# analog_converter.net
KiCad netlist of a schematic drawn in Altium Designer
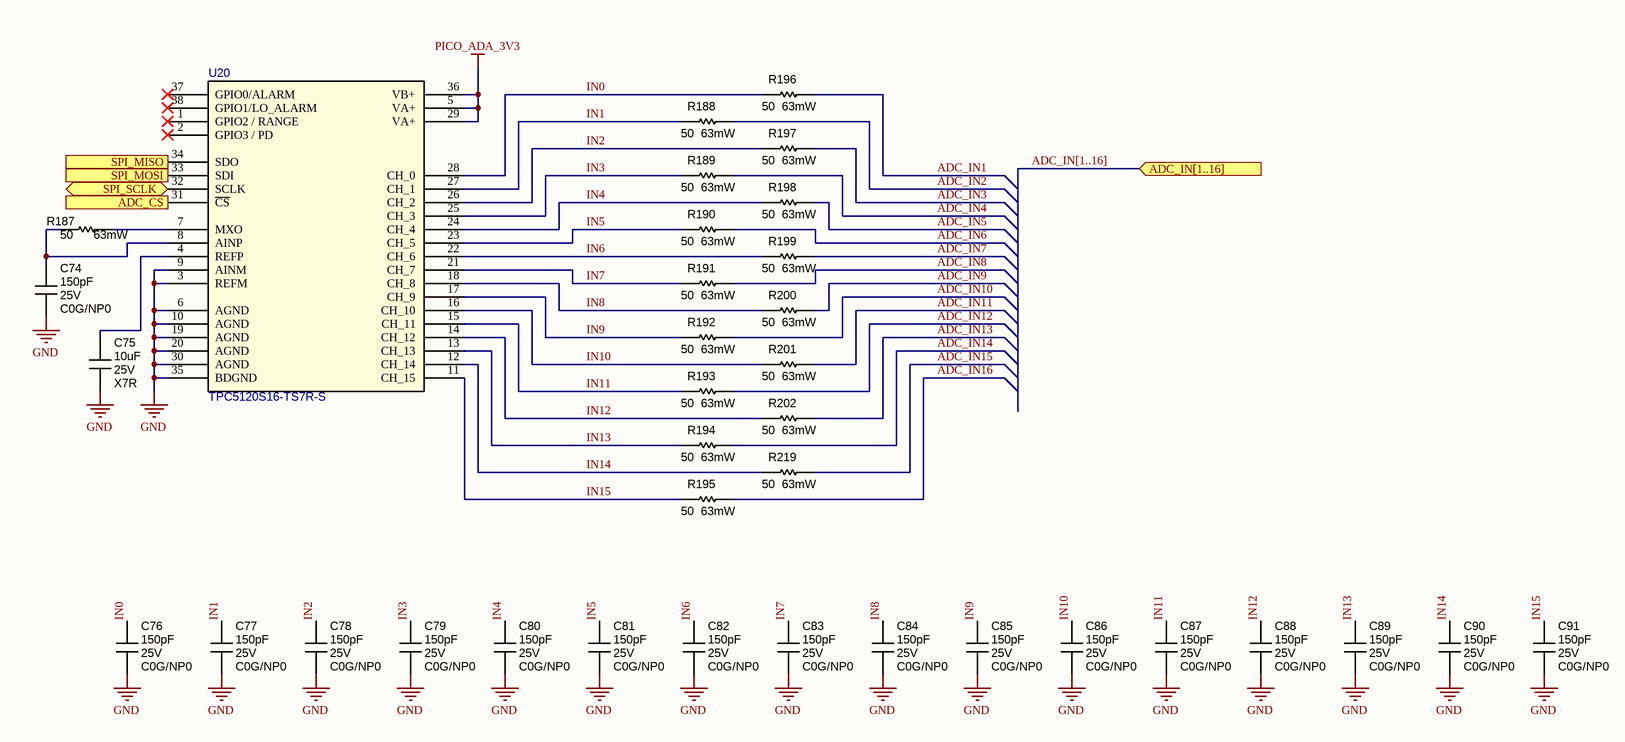
[diagram p0: analog_converter.SchDoc]

(export (version "E")
  (design (tool "Eeschema 10.0.6"))
  (components
    (comp (ref "C74")
      (value "150pF")
      (footprint "CAPC1005X06N")
      (description "CAP CER 150PF 25V C0G/NP0 0402")
      (fields
        (field (name "TOLERANCE") "5%")
        (field (name "MFR") "KEMET")
        (field (name "VOLTAGE RATING") "25V")
        (field (name "TEMP COEFF") "C0G/NP0")
      )
      (libsource (lib "General_Library") (part "CMP-004-0079"))
    )
    (comp (ref "C75")
      (value "10uF")
      (footprint "CAPC3225X28N")
      (description "CAP CER 10UF 25V X7R 1206")
      (fields
        (field (name "TOLERANCE") "10%")
        (field (name "MFR") "Murata Electronics")
        (field (name "VOLTAGE RATING") "25V")
        (field (name "TEMP COEFF") "X7R")
      )
      (libsource (lib "General_Library") (part "CMP-004-0004"))
    )
    (comp (ref "C76")
      (value "150pF")
      (footprint "CAPC1005X06N")
      (description "CAP CER 150PF 25V C0G/NP0 0402")
      (fields
        (field (name "TOLERANCE") "5%")
        (field (name "MFR") "KEMET")
        (field (name "VOLTAGE RATING") "25V")
        (field (name "TEMP COEFF") "C0G/NP0")
      )
      (libsource (lib "General_Library") (part "CMP-004-0079"))
    )
    (comp (ref "C77")
      (value "150pF")
      (footprint "CAPC1005X06N")
      (description "CAP CER 150PF 25V C0G/NP0 0402")
      (fields
        (field (name "TOLERANCE") "5%")
        (field (name "MFR") "KEMET")
        (field (name "VOLTAGE RATING") "25V")
        (field (name "TEMP COEFF") "C0G/NP0")
      )
      (libsource (lib "General_Library") (part "CMP-004-0079"))
    )
    (comp (ref "C78")
      (value "150pF")
      (footprint "CAPC1005X06N")
      (description "CAP CER 150PF 25V C0G/NP0 0402")
      (fields
        (field (name "TOLERANCE") "5%")
        (field (name "MFR") "KEMET")
        (field (name "VOLTAGE RATING") "25V")
        (field (name "TEMP COEFF") "C0G/NP0")
      )
      (libsource (lib "General_Library") (part "CMP-004-0079"))
    )
    (comp (ref "C79")
      (value "150pF")
      (footprint "CAPC1005X06N")
      (description "CAP CER 150PF 25V C0G/NP0 0402")
      (fields
        (field (name "TOLERANCE") "5%")
        (field (name "MFR") "KEMET")
        (field (name "VOLTAGE RATING") "25V")
        (field (name "TEMP COEFF") "C0G/NP0")
      )
      (libsource (lib "General_Library") (part "CMP-004-0079"))
    )
    (comp (ref "C80")
      (value "150pF")
      (footprint "CAPC1005X06N")
      (description "CAP CER 150PF 25V C0G/NP0 0402")
      (fields
        (field (name "TOLERANCE") "5%")
        (field (name "MFR") "KEMET")
        (field (name "VOLTAGE RATING") "25V")
        (field (name "TEMP COEFF") "C0G/NP0")
      )
      (libsource (lib "General_Library") (part "CMP-004-0079"))
    )
    (comp (ref "C81")
      (value "150pF")
      (footprint "CAPC1005X06N")
      (description "CAP CER 150PF 25V C0G/NP0 0402")
      (fields
        (field (name "TOLERANCE") "5%")
        (field (name "MFR") "KEMET")
        (field (name "VOLTAGE RATING") "25V")
        (field (name "TEMP COEFF") "C0G/NP0")
      )
      (libsource (lib "General_Library") (part "CMP-004-0079"))
    )
    (comp (ref "C82")
      (value "150pF")
      (footprint "CAPC1005X06N")
      (description "CAP CER 150PF 25V C0G/NP0 0402")
      (fields
        (field (name "TOLERANCE") "5%")
        (field (name "MFR") "KEMET")
        (field (name "VOLTAGE RATING") "25V")
        (field (name "TEMP COEFF") "C0G/NP0")
      )
      (libsource (lib "General_Library") (part "CMP-004-0079"))
    )
    (comp (ref "C83")
      (value "150pF")
      (footprint "CAPC1005X06N")
      (description "CAP CER 150PF 25V C0G/NP0 0402")
      (fields
        (field (name "TOLERANCE") "5%")
        (field (name "MFR") "KEMET")
        (field (name "VOLTAGE RATING") "25V")
        (field (name "TEMP COEFF") "C0G/NP0")
      )
      (libsource (lib "General_Library") (part "CMP-004-0079"))
    )
    (comp (ref "C84")
      (value "150pF")
      (footprint "CAPC1005X06N")
      (description "CAP CER 150PF 25V C0G/NP0 0402")
      (fields
        (field (name "TOLERANCE") "5%")
        (field (name "MFR") "KEMET")
        (field (name "VOLTAGE RATING") "25V")
        (field (name "TEMP COEFF") "C0G/NP0")
      )
      (libsource (lib "General_Library") (part "CMP-004-0079"))
    )
    (comp (ref "C85")
      (value "150pF")
      (footprint "CAPC1005X06N")
      (description "CAP CER 150PF 25V C0G/NP0 0402")
      (fields
        (field (name "TOLERANCE") "5%")
        (field (name "MFR") "KEMET")
        (field (name "VOLTAGE RATING") "25V")
        (field (name "TEMP COEFF") "C0G/NP0")
      )
      (libsource (lib "General_Library") (part "CMP-004-0079"))
    )
    (comp (ref "C86")
      (value "150pF")
      (footprint "CAPC1005X06N")
      (description "CAP CER 150PF 25V C0G/NP0 0402")
      (fields
        (field (name "TOLERANCE") "5%")
        (field (name "MFR") "KEMET")
        (field (name "VOLTAGE RATING") "25V")
        (field (name "TEMP COEFF") "C0G/NP0")
      )
      (libsource (lib "General_Library") (part "CMP-004-0079"))
    )
    (comp (ref "C87")
      (value "150pF")
      (footprint "CAPC1005X06N")
      (description "CAP CER 150PF 25V C0G/NP0 0402")
      (fields
        (field (name "TOLERANCE") "5%")
        (field (name "MFR") "KEMET")
        (field (name "VOLTAGE RATING") "25V")
        (field (name "TEMP COEFF") "C0G/NP0")
      )
      (libsource (lib "General_Library") (part "CMP-004-0079"))
    )
    (comp (ref "C88")
      (value "150pF")
      (footprint "CAPC1005X06N")
      (description "CAP CER 150PF 25V C0G/NP0 0402")
      (fields
        (field (name "TOLERANCE") "5%")
        (field (name "MFR") "KEMET")
        (field (name "VOLTAGE RATING") "25V")
        (field (name "TEMP COEFF") "C0G/NP0")
      )
      (libsource (lib "General_Library") (part "CMP-004-0079"))
    )
    (comp (ref "C89")
      (value "150pF")
      (footprint "CAPC1005X06N")
      (description "CAP CER 150PF 25V C0G/NP0 0402")
      (fields
        (field (name "TOLERANCE") "5%")
        (field (name "MFR") "KEMET")
        (field (name "VOLTAGE RATING") "25V")
        (field (name "TEMP COEFF") "C0G/NP0")
      )
      (libsource (lib "General_Library") (part "CMP-004-0079"))
    )
    (comp (ref "C90")
      (value "150pF")
      (footprint "CAPC1005X06N")
      (description "CAP CER 150PF 25V C0G/NP0 0402")
      (fields
        (field (name "TOLERANCE") "5%")
        (field (name "MFR") "KEMET")
        (field (name "VOLTAGE RATING") "25V")
        (field (name "TEMP COEFF") "C0G/NP0")
      )
      (libsource (lib "General_Library") (part "CMP-004-0079"))
    )
    (comp (ref "C91")
      (value "150pF")
      (footprint "CAPC1005X06N")
      (description "CAP CER 150PF 25V C0G/NP0 0402")
      (fields
        (field (name "TOLERANCE") "5%")
        (field (name "MFR") "KEMET")
        (field (name "VOLTAGE RATING") "25V")
        (field (name "TEMP COEFF") "C0G/NP0")
      )
      (libsource (lib "General_Library") (part "CMP-004-0079"))
    )
    (comp (ref "R187")
      (value "50")
      (footprint "RESC1005X04N")
      (description "RES SMD 50R OHM 1% 1/16W 0402")
      (fields
        (field (name "TOLERANCE") "1%")
        (field (name "MFR") "KOA Speer Electronics")
        (field (name "WATTAGE") "63mW")
      )
      (libsource (lib "General_Library") (part "CMP-025-0174"))
    )
    (comp (ref "R188")
      (value "50")
      (footprint "RESC1005X04N")
      (description "RES SMD 50R OHM 1% 1/16W 0402")
      (fields
        (field (name "TOLERANCE") "1%")
        (field (name "MFR") "KOA Speer Electronics")
        (field (name "WATTAGE") "63mW")
      )
      (libsource (lib "General_Library") (part "CMP-025-0174"))
    )
    (comp (ref "R189")
      (value "50")
      (footprint "RESC1005X04N")
      (description "RES SMD 50R OHM 1% 1/16W 0402")
      (fields
        (field (name "TOLERANCE") "1%")
        (field (name "MFR") "KOA Speer Electronics")
        (field (name "WATTAGE") "63mW")
      )
      (libsource (lib "General_Library") (part "CMP-025-0174"))
    )
    (comp (ref "R190")
      (value "50")
      (footprint "RESC1005X04N")
      (description "RES SMD 50R OHM 1% 1/16W 0402")
      (fields
        (field (name "TOLERANCE") "1%")
        (field (name "MFR") "KOA Speer Electronics")
        (field (name "WATTAGE") "63mW")
      )
      (libsource (lib "General_Library") (part "CMP-025-0174"))
    )
    (comp (ref "R191")
      (value "50")
      (footprint "RESC1005X04N")
      (description "RES SMD 50R OHM 1% 1/16W 0402")
      (fields
        (field (name "TOLERANCE") "1%")
        (field (name "MFR") "KOA Speer Electronics")
        (field (name "WATTAGE") "63mW")
      )
      (libsource (lib "General_Library") (part "CMP-025-0174"))
    )
    (comp (ref "R192")
      (value "50")
      (footprint "RESC1005X04N")
      (description "RES SMD 50R OHM 1% 1/16W 0402")
      (fields
        (field (name "TOLERANCE") "1%")
        (field (name "MFR") "KOA Speer Electronics")
        (field (name "WATTAGE") "63mW")
      )
      (libsource (lib "General_Library") (part "CMP-025-0174"))
    )
    (comp (ref "R193")
      (value "50")
      (footprint "RESC1005X04N")
      (description "RES SMD 50R OHM 1% 1/16W 0402")
      (fields
        (field (name "TOLERANCE") "1%")
        (field (name "MFR") "KOA Speer Electronics")
        (field (name "WATTAGE") "63mW")
      )
      (libsource (lib "General_Library") (part "CMP-025-0174"))
    )
    (comp (ref "R194")
      (value "50")
      (footprint "RESC1005X04N")
      (description "RES SMD 50R OHM 1% 1/16W 0402")
      (fields
        (field (name "TOLERANCE") "1%")
        (field (name "MFR") "KOA Speer Electronics")
        (field (name "WATTAGE") "63mW")
      )
      (libsource (lib "General_Library") (part "CMP-025-0174"))
    )
    (comp (ref "R195")
      (value "50")
      (footprint "RESC1005X04N")
      (description "RES SMD 50R OHM 1% 1/16W 0402")
      (fields
        (field (name "TOLERANCE") "1%")
        (field (name "MFR") "KOA Speer Electronics")
        (field (name "WATTAGE") "63mW")
      )
      (libsource (lib "General_Library") (part "CMP-025-0174"))
    )
    (comp (ref "R196")
      (value "50")
      (footprint "RESC1005X04N")
      (description "RES SMD 50R OHM 1% 1/16W 0402")
      (fields
        (field (name "TOLERANCE") "1%")
        (field (name "MFR") "KOA Speer Electronics")
        (field (name "WATTAGE") "63mW")
      )
      (libsource (lib "General_Library") (part "CMP-025-0174"))
    )
    (comp (ref "R197")
      (value "50")
      (footprint "RESC1005X04N")
      (description "RES SMD 50R OHM 1% 1/16W 0402")
      (fields
        (field (name "TOLERANCE") "1%")
        (field (name "MFR") "KOA Speer Electronics")
        (field (name "WATTAGE") "63mW")
      )
      (libsource (lib "General_Library") (part "CMP-025-0174"))
    )
    (comp (ref "R198")
      (value "50")
      (footprint "RESC1005X04N")
      (description "RES SMD 50R OHM 1% 1/16W 0402")
      (fields
        (field (name "TOLERANCE") "1%")
        (field (name "MFR") "KOA Speer Electronics")
        (field (name "WATTAGE") "63mW")
      )
      (libsource (lib "General_Library") (part "CMP-025-0174"))
    )
    (comp (ref "R199")
      (value "50")
      (footprint "RESC1005X04N")
      (description "RES SMD 50R OHM 1% 1/16W 0402")
      (fields
        (field (name "TOLERANCE") "1%")
        (field (name "MFR") "KOA Speer Electronics")
        (field (name "WATTAGE") "63mW")
      )
      (libsource (lib "General_Library") (part "CMP-025-0174"))
    )
    (comp (ref "R200")
      (value "50")
      (footprint "RESC1005X04N")
      (description "RES SMD 50R OHM 1% 1/16W 0402")
      (fields
        (field (name "TOLERANCE") "1%")
        (field (name "MFR") "KOA Speer Electronics")
        (field (name "WATTAGE") "63mW")
      )
      (libsource (lib "General_Library") (part "CMP-025-0174"))
    )
    (comp (ref "R201")
      (value "50")
      (footprint "RESC1005X04N")
      (description "RES SMD 50R OHM 1% 1/16W 0402")
      (fields
        (field (name "TOLERANCE") "1%")
        (field (name "MFR") "KOA Speer Electronics")
        (field (name "WATTAGE") "63mW")
      )
      (libsource (lib "General_Library") (part "CMP-025-0174"))
    )
    (comp (ref "R202")
      (value "50")
      (footprint "RESC1005X04N")
      (description "RES SMD 50R OHM 1% 1/16W 0402")
      (fields
        (field (name "TOLERANCE") "1%")
        (field (name "MFR") "KOA Speer Electronics")
        (field (name "WATTAGE") "63mW")
      )
      (libsource (lib "General_Library") (part "CMP-025-0174"))
    )
    (comp (ref "R219")
      (value "50")
      (footprint "RESC1005X04N")
      (description "RES SMD 50R OHM 1% 1/16W 0402")
      (fields
        (field (name "TOLERANCE") "1%")
        (field (name "MFR") "KOA Speer Electronics")
        (field (name "WATTAGE") "63mW")
      )
      (libsource (lib "General_Library") (part "CMP-025-0174"))
    )
    (comp (ref "U20")
      (value "TPC5120S16-TS7R-S")
      (footprint "Footprints:TSSOP50P640X120-38N")
      (description "IC 12 BIT ANALOG TO DIGITAL CONVERT SPI")
      (fields (field (name "MFR") "3PEAK"))
      (libsource (lib "Symbols") (part "CMP-017-0116"))
    )
  )
  (nets
    (net (code "1") (name "/ADC_CS") (class "Default")
      (node (ref "U20") (pin "31") (pinfunction "~{CS}_31") (pintype "passive"))
    )
    (net (code "2") (name "/ADC_IN1") (class "Default")
      (node (ref "R196") (pin "2") (pinfunction "2_2") (pintype "passive"))
    )
    (net (code "3") (name "/ADC_IN2") (class "Default")
      (node (ref "R188") (pin "2") (pinfunction "2_2") (pintype "passive"))
    )
    (net (code "4") (name "/ADC_IN3") (class "Default")
      (node (ref "R197") (pin "2") (pinfunction "2_2") (pintype "passive"))
    )
    (net (code "5") (name "/ADC_IN4") (class "Default")
      (node (ref "R189") (pin "2") (pinfunction "2_2") (pintype "passive"))
    )
    (net (code "6") (name "/ADC_IN5") (class "Default")
      (node (ref "R198") (pin "2") (pinfunction "2_2") (pintype "passive"))
    )
    (net (code "7") (name "/ADC_IN6") (class "Default")
      (node (ref "R190") (pin "2") (pinfunction "2_2") (pintype "passive"))
    )
    (net (code "8") (name "/ADC_IN7") (class "Default")
      (node (ref "R199") (pin "2") (pinfunction "2_2") (pintype "passive"))
    )
    (net (code "9") (name "/ADC_IN8") (class "Default")
      (node (ref "R191") (pin "2") (pinfunction "2_2") (pintype "passive"))
    )
    (net (code "10") (name "/ADC_IN9") (class "Default")
      (node (ref "R200") (pin "2") (pinfunction "2_2") (pintype "passive"))
    )
    (net (code "11") (name "/ADC_IN10") (class "Default")
      (node (ref "R192") (pin "2") (pinfunction "2_2") (pintype "passive"))
    )
    (net (code "12") (name "/ADC_IN11") (class "Default")
      (node (ref "R201") (pin "2") (pinfunction "2_2") (pintype "passive"))
    )
    (net (code "13") (name "/ADC_IN12") (class "Default")
      (node (ref "R193") (pin "2") (pinfunction "2_2") (pintype "passive"))
    )
    (net (code "14") (name "/ADC_IN13") (class "Default")
      (node (ref "R202") (pin "2") (pinfunction "2_2") (pintype "passive"))
    )
    (net (code "15") (name "/ADC_IN14") (class "Default")
      (node (ref "R194") (pin "2") (pinfunction "2_2") (pintype "passive"))
    )
    (net (code "16") (name "/ADC_IN15") (class "Default")
      (node (ref "R219") (pin "2") (pinfunction "2_2") (pintype "passive"))
    )
    (net (code "17") (name "/ADC_IN16") (class "Default")
      (node (ref "R195") (pin "2") (pinfunction "2_2") (pintype "passive"))
    )
    (net (code "19") (name "/IN0") (class "Default")
      (node (ref "C76") (pin "1") (pinfunction "1_1") (pintype "passive"))
      (node (ref "R196") (pin "1") (pinfunction "1_1") (pintype "passive"))
      (node (ref "U20") (pin "28") (pinfunction "CH_0_28") (pintype "passive"))
    )
    (net (code "20") (name "/IN1") (class "Default")
      (node (ref "C77") (pin "1") (pinfunction "1_1") (pintype "passive"))
      (node (ref "R188") (pin "1") (pinfunction "1_1") (pintype "passive"))
      (node (ref "U20") (pin "27") (pinfunction "CH_1_27") (pintype "passive"))
    )
    (net (code "21") (name "/IN2") (class "Default")
      (node (ref "C78") (pin "1") (pinfunction "1_1") (pintype "passive"))
      (node (ref "R197") (pin "1") (pinfunction "1_1") (pintype "passive"))
      (node (ref "U20") (pin "26") (pinfunction "CH_2_26") (pintype "passive"))
    )
    (net (code "22") (name "/IN3") (class "Default")
      (node (ref "C79") (pin "1") (pinfunction "1_1") (pintype "passive"))
      (node (ref "R189") (pin "1") (pinfunction "1_1") (pintype "passive"))
      (node (ref "U20") (pin "25") (pinfunction "CH_3_25") (pintype "passive"))
    )
    (net (code "23") (name "/IN4") (class "Default")
      (node (ref "C80") (pin "1") (pinfunction "1_1") (pintype "passive"))
      (node (ref "R198") (pin "1") (pinfunction "1_1") (pintype "passive"))
      (node (ref "U20") (pin "24") (pinfunction "CH_4_24") (pintype "passive"))
    )
    (net (code "24") (name "/IN5") (class "Default")
      (node (ref "C81") (pin "1") (pinfunction "1_1") (pintype "passive"))
      (node (ref "R190") (pin "1") (pinfunction "1_1") (pintype "passive"))
      (node (ref "U20") (pin "23") (pinfunction "CH_5_23") (pintype "passive"))
    )
    (net (code "25") (name "/IN6") (class "Default")
      (node (ref "C82") (pin "1") (pinfunction "1_1") (pintype "passive"))
      (node (ref "R199") (pin "1") (pinfunction "1_1") (pintype "passive"))
      (node (ref "U20") (pin "22") (pinfunction "CH_6_22") (pintype "passive"))
    )
    (net (code "26") (name "/IN7") (class "Default")
      (node (ref "C83") (pin "1") (pinfunction "1_1") (pintype "passive"))
      (node (ref "R191") (pin "1") (pinfunction "1_1") (pintype "passive"))
      (node (ref "U20") (pin "21") (pinfunction "CH_7_21") (pintype "passive"))
    )
    (net (code "27") (name "/IN8") (class "Default")
      (node (ref "C84") (pin "1") (pinfunction "1_1") (pintype "passive"))
      (node (ref "R200") (pin "1") (pinfunction "1_1") (pintype "passive"))
      (node (ref "U20") (pin "18") (pinfunction "CH_8_18") (pintype "passive"))
    )
    (net (code "28") (name "/IN9") (class "Default")
      (node (ref "C85") (pin "1") (pinfunction "1_1") (pintype "passive"))
      (node (ref "R192") (pin "1") (pinfunction "1_1") (pintype "passive"))
      (node (ref "U20") (pin "17") (pinfunction "CH_9_17") (pintype "passive"))
    )
    (net (code "29") (name "/IN10") (class "Default")
      (node (ref "C86") (pin "1") (pinfunction "1_1") (pintype "passive"))
      (node (ref "R201") (pin "1") (pinfunction "1_1") (pintype "passive"))
      (node (ref "U20") (pin "16") (pinfunction "CH_10_16") (pintype "passive"))
    )
    (net (code "30") (name "/IN11") (class "Default")
      (node (ref "C87") (pin "1") (pinfunction "1_1") (pintype "passive"))
      (node (ref "R193") (pin "1") (pinfunction "1_1") (pintype "passive"))
      (node (ref "U20") (pin "15") (pinfunction "CH_11_15") (pintype "passive"))
    )
    (net (code "31") (name "/IN12") (class "Default")
      (node (ref "C88") (pin "1") (pinfunction "1_1") (pintype "passive"))
      (node (ref "R202") (pin "1") (pinfunction "1_1") (pintype "passive"))
      (node (ref "U20") (pin "14") (pinfunction "CH_12_14") (pintype "passive"))
    )
    (net (code "32") (name "/IN13") (class "Default")
      (node (ref "C89") (pin "1") (pinfunction "1_1") (pintype "passive"))
      (node (ref "R194") (pin "1") (pinfunction "1_1") (pintype "passive"))
      (node (ref "U20") (pin "13") (pinfunction "CH_13_13") (pintype "passive"))
    )
    (net (code "33") (name "/IN14") (class "Default")
      (node (ref "C90") (pin "1") (pinfunction "1_1") (pintype "passive"))
      (node (ref "R219") (pin "1") (pinfunction "1_1") (pintype "passive"))
      (node (ref "U20") (pin "12") (pinfunction "CH_14_12") (pintype "passive"))
    )
    (net (code "34") (name "/IN15") (class "Default")
      (node (ref "C91") (pin "1") (pinfunction "1_1") (pintype "passive"))
      (node (ref "R195") (pin "1") (pinfunction "1_1") (pintype "passive"))
      (node (ref "U20") (pin "11") (pinfunction "CH_15_11") (pintype "passive"))
    )
    (net (code "35") (name "/SPI_MISO") (class "Default")
      (node (ref "U20") (pin "34") (pinfunction "SDO_34") (pintype "passive"))
    )
    (net (code "36") (name "/SPI_MOSI") (class "Default")
      (node (ref "U20") (pin "33") (pinfunction "SDI_33") (pintype "passive"))
    )
    (net (code "37") (name "/SPI_SCLK") (class "Default")
      (node (ref "U20") (pin "32") (pinfunction "SCLK_32") (pintype "passive"))
    )
    (net (code "38") (name "GND") (class "Default")
      (node (ref "C74") (pin "2") (pinfunction "2_2") (pintype "passive"))
      (node (ref "C75") (pin "2") (pinfunction "2_2") (pintype "passive"))
      (node (ref "C76") (pin "2") (pinfunction "2_2") (pintype "passive"))
      (node (ref "C77") (pin "2") (pinfunction "2_2") (pintype "passive"))
      (node (ref "C78") (pin "2") (pinfunction "2_2") (pintype "passive"))
      (node (ref "C79") (pin "2") (pinfunction "2_2") (pintype "passive"))
      (node (ref "C80") (pin "2") (pinfunction "2_2") (pintype "passive"))
      (node (ref "C81") (pin "2") (pinfunction "2_2") (pintype "passive"))
      (node (ref "C82") (pin "2") (pinfunction "2_2") (pintype "passive"))
      (node (ref "C83") (pin "2") (pinfunction "2_2") (pintype "passive"))
      (node (ref "C84") (pin "2") (pinfunction "2_2") (pintype "passive"))
      (node (ref "C85") (pin "2") (pinfunction "2_2") (pintype "passive"))
      (node (ref "C86") (pin "2") (pinfunction "2_2") (pintype "passive"))
      (node (ref "C87") (pin "2") (pinfunction "2_2") (pintype "passive"))
      (node (ref "C88") (pin "2") (pinfunction "2_2") (pintype "passive"))
      (node (ref "C89") (pin "2") (pinfunction "2_2") (pintype "passive"))
      (node (ref "C90") (pin "2") (pinfunction "2_2") (pintype "passive"))
      (node (ref "C91") (pin "2") (pinfunction "2_2") (pintype "passive"))
      (node (ref "U20") (pin "10") (pinfunction "AGND_10") (pintype "power_in"))
      (node (ref "U20") (pin "19") (pinfunction "AGND_19") (pintype "power_in"))
      (node (ref "U20") (pin "20") (pinfunction "AGND_20") (pintype "power_in"))
      (node (ref "U20") (pin "3") (pinfunction "REFM_3") (pintype "passive"))
      (node (ref "U20") (pin "30") (pinfunction "AGND_30") (pintype "power_in"))
      (node (ref "U20") (pin "35") (pinfunction "BDGND_35") (pintype "power_in"))
      (node (ref "U20") (pin "6") (pinfunction "AGND_6") (pintype "power_in"))
      (node (ref "U20") (pin "9") (pinfunction "AINM_9") (pintype "passive"))
    )
    (net (code "39") (name "Net-(U20-AINP)") (class "Default")
      (node (ref "C74") (pin "1") (pinfunction "1_1") (pintype "passive"))
      (node (ref "R187") (pin "1") (pinfunction "1_1") (pintype "passive"))
      (node (ref "U20") (pin "8") (pinfunction "AINP_8") (pintype "passive"))
    )
    (net (code "40") (name "Net-(U20-MXO)") (class "Default")
      (node (ref "R187") (pin "2") (pinfunction "2_2") (pintype "passive"))
      (node (ref "U20") (pin "7") (pinfunction "MXO_7") (pintype "passive"))
    )
    (net (code "41") (name "Net-(U20-REFP)") (class "Default")
      (node (ref "C75") (pin "1") (pinfunction "1_1") (pintype "passive"))
      (node (ref "U20") (pin "4") (pinfunction "REFP_4") (pintype "passive"))
    )
    (net (code "42") (name "PICO_ADA_3V3") (class "Default")
      (node (ref "U20") (pin "29") (pinfunction "VA+_29") (pintype "power_in"))
      (node (ref "U20") (pin "36") (pinfunction "VB+_36") (pintype "power_in"))
      (node (ref "U20") (pin "5") (pinfunction "VA+_5") (pintype "power_in"))
    )
    (net (code "43") (name "unconnected-(U20-GPIO0{slash}ALARM-Pad37)") (class "Default")
      (node (ref "U20") (pin "37") (pinfunction "GPIO0/ALARM_37") (pintype "passive+no_connect"))
    )
    (net (code "44") (name "unconnected-(U20-GPIO1{slash}LO_ALARM-Pad38)") (class "Default")
      (node (ref "U20") (pin "38") (pinfunction "GPIO1/LO_ALARM_38") (pintype "passive+no_connect"))
    )
    (net (code "45") (name "unconnected-(U20-GPIO2_{slash}_RANGE-Pad1)") (class "Default")
      (node (ref "U20") (pin "1") (pinfunction "GPIO2_/_RANGE_1") (pintype "passive+no_connect"))
    )
    (net (code "46") (name "unconnected-(U20-GPIO3_{slash}_PD-Pad2)") (class "Default")
      (node (ref "U20") (pin "2") (pinfunction "GPIO3_/_PD_2") (pintype "passive+no_connect"))
    )
  )
)
